# PowerConversionBoard.net
KiCad netlist of a schematic drawn in EAGLE
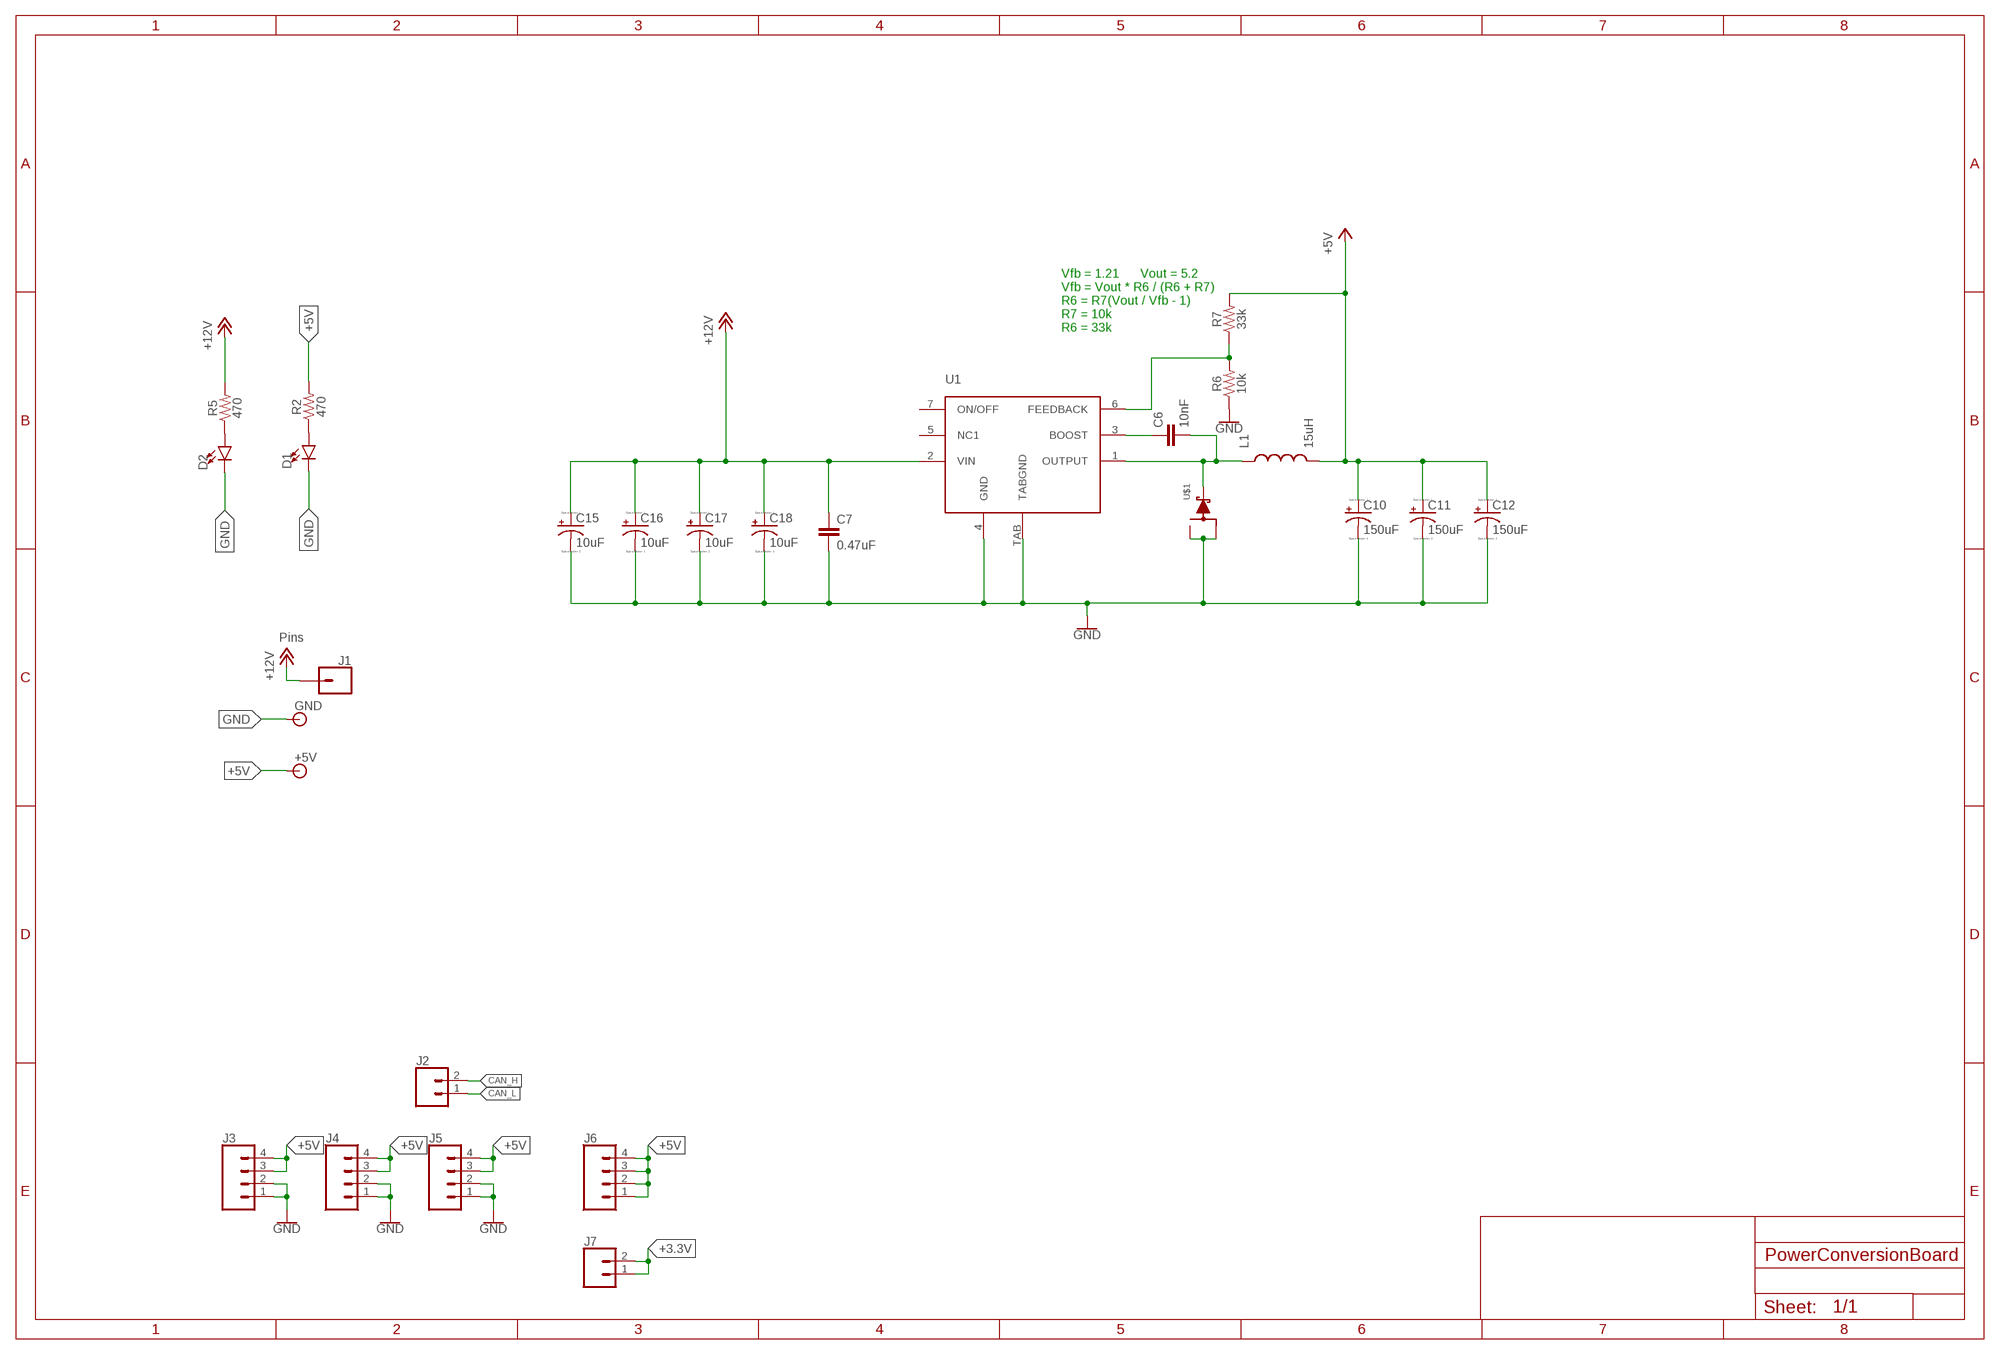
[diagram p0: schematic, sheet 1, part 1 of 3]
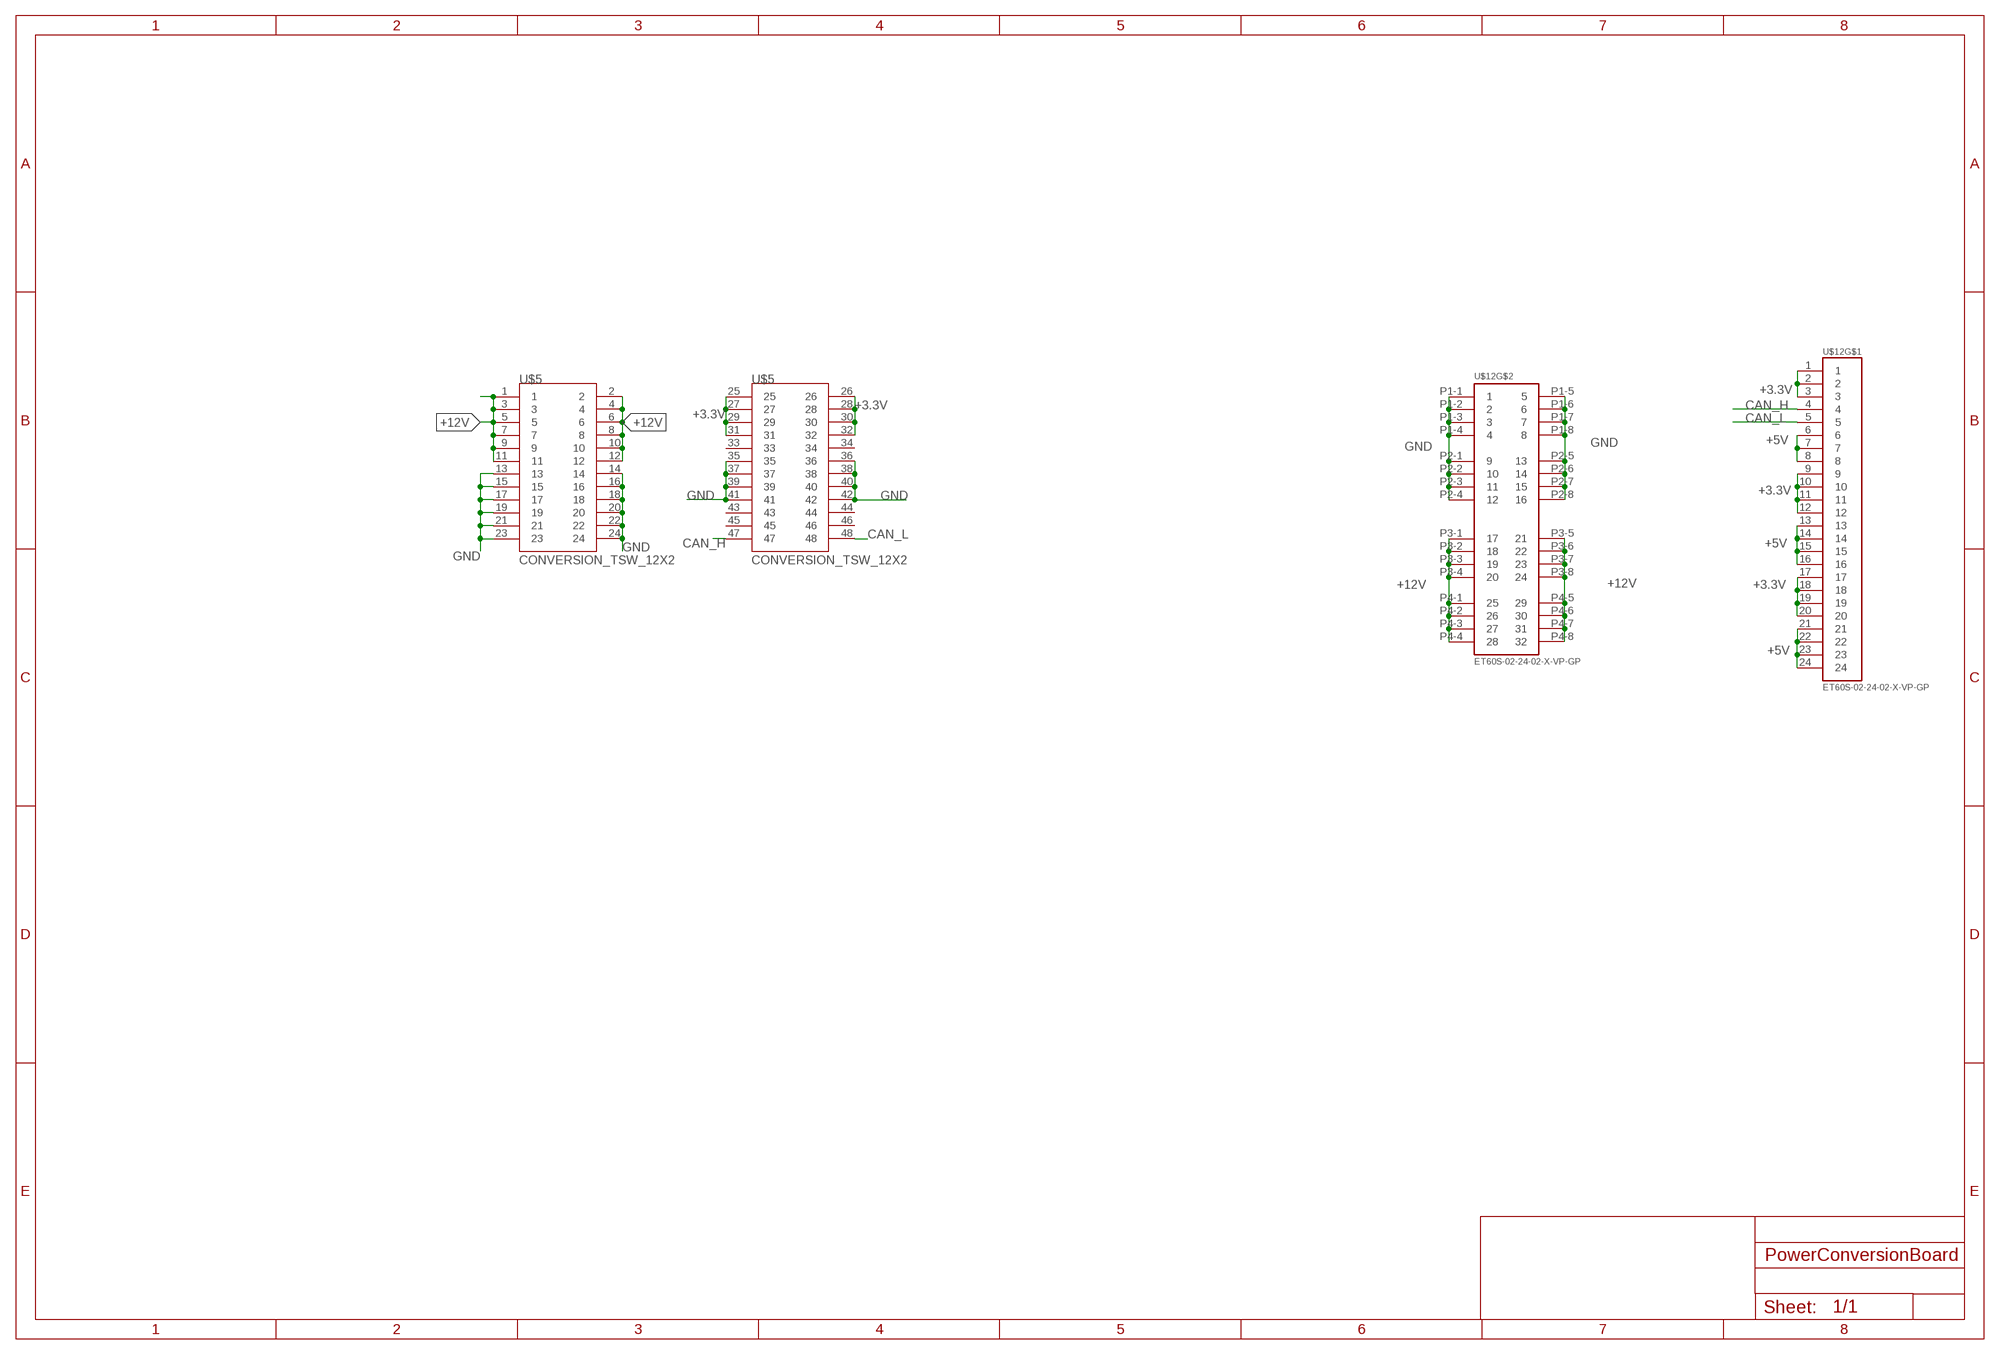
[diagram p1: schematic, sheet 1, part 2 of 3]
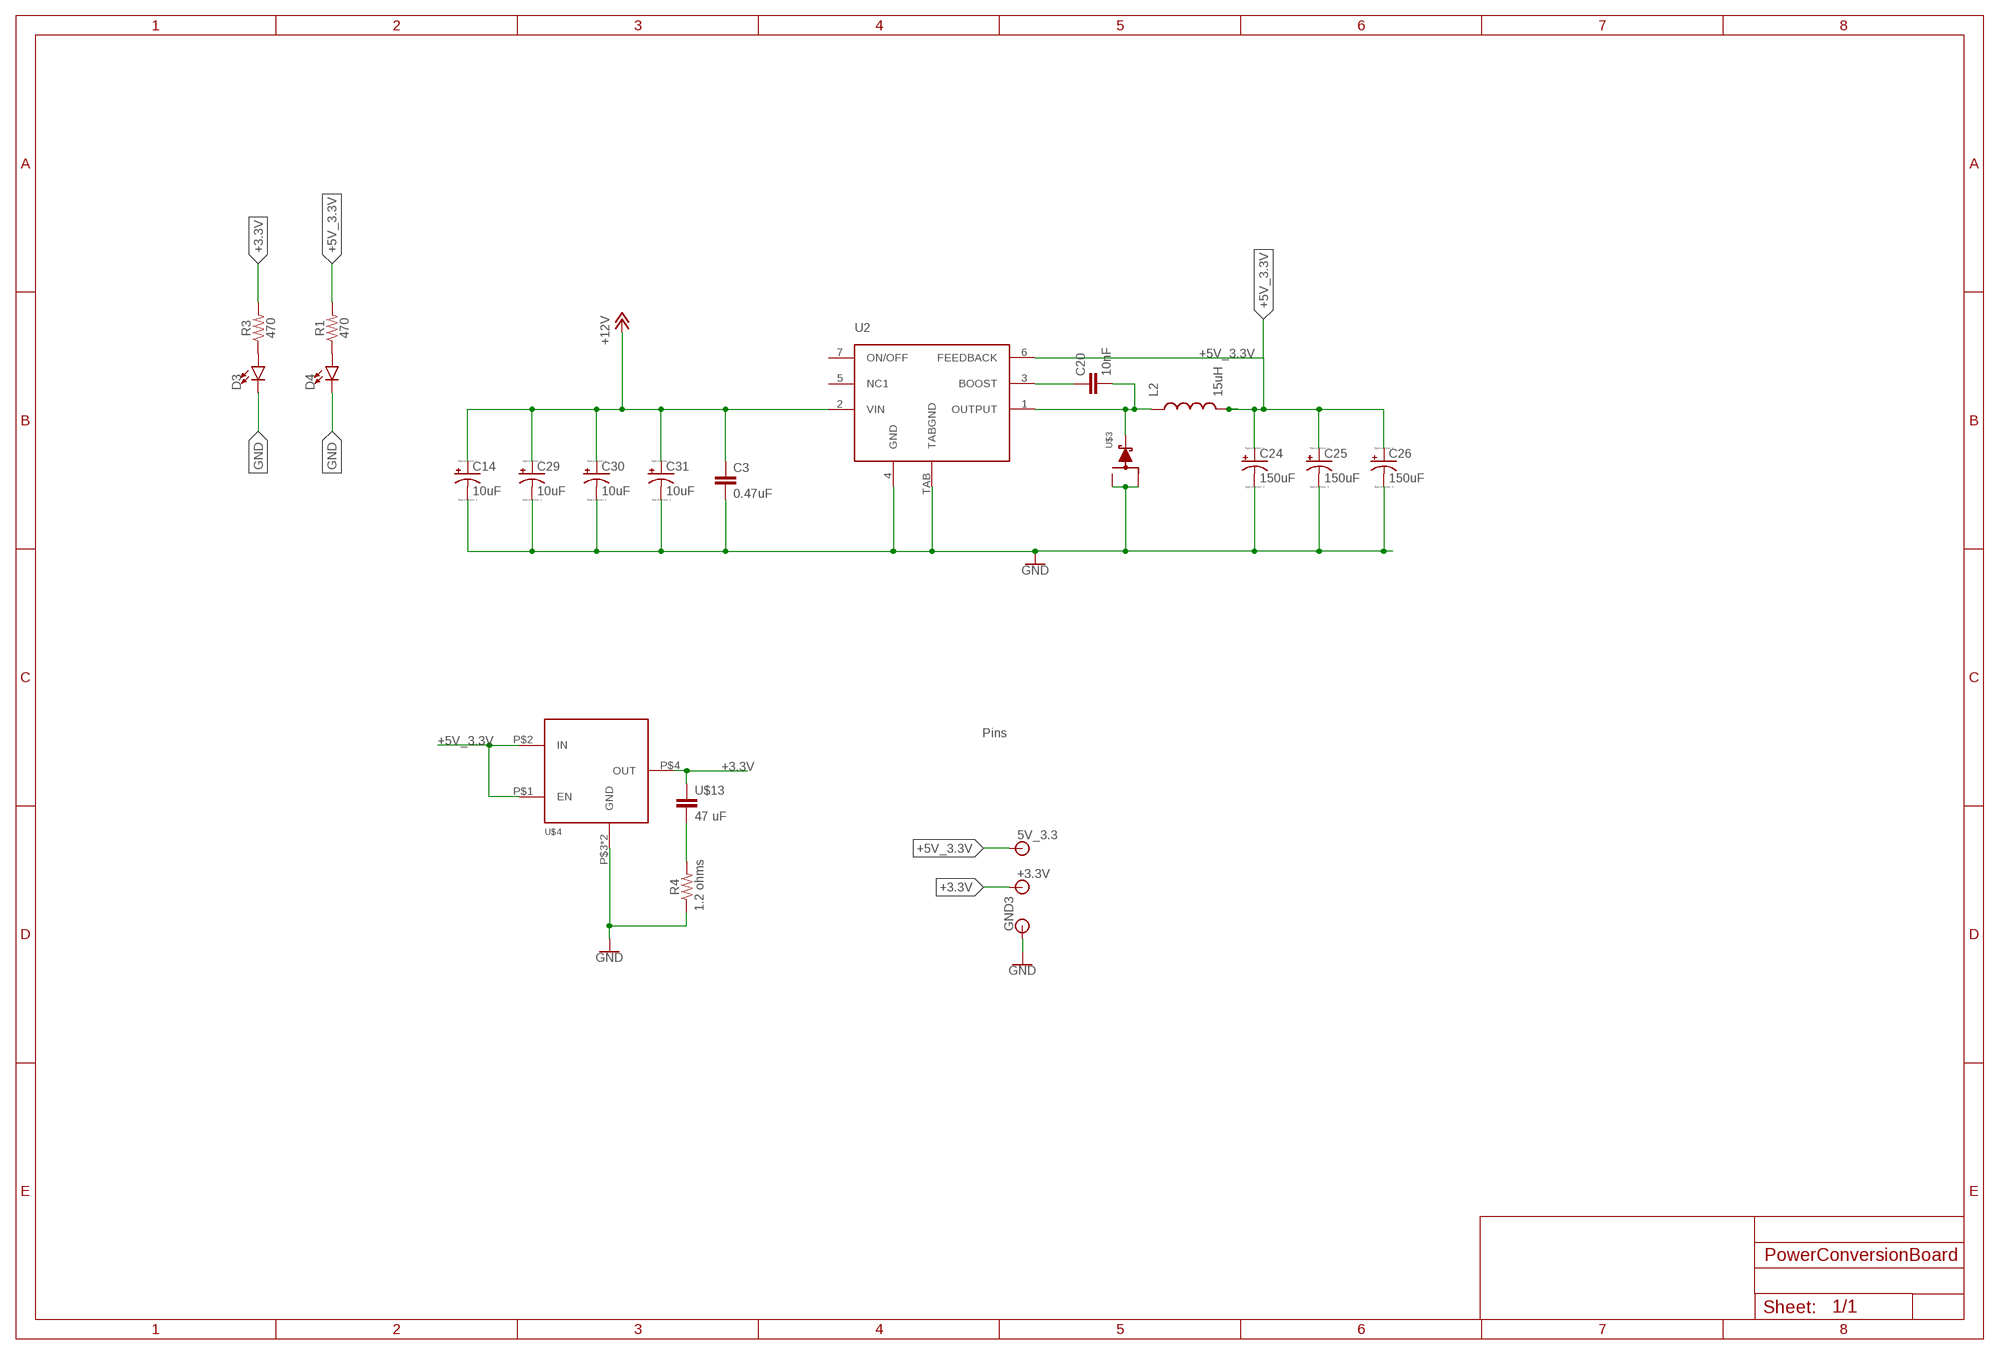
[diagram p2: schematic, sheet 1, part 3 of 3]

(export (version "E")
  (design (tool "Eeschema 10.0.6"))
  (components
    (comp (ref "+3.3V")
      (value "BANANA_CONN")
      (footprint "eagle-import:BANANA_CONN")
      (libsource (lib "eagle-import") (part "BANANA_CONN"))
    )
    (comp (ref "+5V")
      (value "BANANA_CONN")
      (footprint "eagle-import:BANANA_CONN")
      (libsource (lib "eagle-import") (part "BANANA_CONN"))
    )
    (comp (ref "5V_3.3")
      (value "BANANA_CONN")
      (footprint "eagle-import:BANANA_CONN")
      (libsource (lib "eagle-import") (part "BANANA_CONN"))
    )
    (comp (ref "C3")
      (value "0.47uF")
      (footprint "eagle-import:C0603")
      (libsource (lib "eagle-import") (part "C-EUC0603"))
    )
    (comp (ref "C6")
      (value "10nF")
      (footprint "eagle-import:0603")
      (libsource (lib "eagle-import") (part "10NF-0603-50V-10%"))
    )
    (comp (ref "C7")
      (value "0.47uF")
      (footprint "eagle-import:C0603")
      (libsource (lib "eagle-import") (part "C-EUC0603"))
    )
    (comp (ref "C10")
      (value "150uF")
      (footprint "eagle-import:CTAN(7.30_4.30MM)")
      (libsource (lib "eagle-import") (part "C-TANTALUM(10UF_150UF)"))
    )
    (comp (ref "C11")
      (value "150uF")
      (footprint "eagle-import:CTAN(7.30_4.30MM)")
      (libsource (lib "eagle-import") (part "C-TANTALUM(10UF_150UF)"))
    )
    (comp (ref "C12")
      (value "150uF")
      (footprint "eagle-import:CTAN(7.30_4.30MM)")
      (libsource (lib "eagle-import") (part "C-TANTALUM(10UF_150UF)"))
    )
    (comp (ref "C14")
      (value "10uF")
      (footprint "eagle-import:CTAN(7.30_4.30MM)")
      (libsource (lib "eagle-import") (part "C-TANTALUM(10UF_150UF)"))
    )
    (comp (ref "C15")
      (value "10uF")
      (footprint "eagle-import:CTAN(7.30_4.30MM)")
      (libsource (lib "eagle-import") (part "C-TANTALUM(10UF_150UF)"))
    )
    (comp (ref "C16")
      (value "10uF")
      (footprint "eagle-import:CTAN(7.30_4.30MM)")
      (libsource (lib "eagle-import") (part "C-TANTALUM(10UF_150UF)"))
    )
    (comp (ref "C17")
      (value "10uF")
      (footprint "eagle-import:CTAN(7.30_4.30MM)")
      (libsource (lib "eagle-import") (part "C-TANTALUM(10UF_150UF)"))
    )
    (comp (ref "C18")
      (value "10uF")
      (footprint "eagle-import:CTAN(7.30_4.30MM)")
      (libsource (lib "eagle-import") (part "C-TANTALUM(10UF_150UF)"))
    )
    (comp (ref "C20")
      (value "10nF")
      (footprint "eagle-import:0603")
      (libsource (lib "eagle-import") (part "10NF-0603-50V-10%"))
    )
    (comp (ref "C24")
      (value "150uF")
      (footprint "eagle-import:CTAN(7.30_4.30MM)")
      (libsource (lib "eagle-import") (part "C-TANTALUM(10UF_150UF)"))
    )
    (comp (ref "C25")
      (value "150uF")
      (footprint "eagle-import:CTAN(7.30_4.30MM)")
      (libsource (lib "eagle-import") (part "C-TANTALUM(10UF_150UF)"))
    )
    (comp (ref "C26")
      (value "150uF")
      (footprint "eagle-import:CTAN(7.30_4.30MM)")
      (libsource (lib "eagle-import") (part "C-TANTALUM(10UF_150UF)"))
    )
    (comp (ref "C29")
      (value "10uF")
      (footprint "eagle-import:CTAN(7.30_4.30MM)")
      (libsource (lib "eagle-import") (part "C-TANTALUM(10UF_150UF)"))
    )
    (comp (ref "C30")
      (value "10uF")
      (footprint "eagle-import:CTAN(7.30_4.30MM)")
      (libsource (lib "eagle-import") (part "C-TANTALUM(10UF_150UF)"))
    )
    (comp (ref "C31")
      (value "10uF")
      (footprint "eagle-import:CTAN(7.30_4.30MM)")
      (libsource (lib "eagle-import") (part "C-TANTALUM(10UF_150UF)"))
    )
    (comp (ref "D1")
      (value "LED0603")
      (footprint "eagle-import:LED-0603")
      (libsource (lib "eagle-import") (part "LED0603"))
    )
    (comp (ref "D2")
      (value "LED0603")
      (footprint "eagle-import:LED-0603")
      (libsource (lib "eagle-import") (part "LED0603"))
    )
    (comp (ref "D3")
      (value "LED0603")
      (footprint "eagle-import:LED-0603")
      (libsource (lib "eagle-import") (part "LED0603"))
    )
    (comp (ref "D4")
      (value "LED0603")
      (footprint "eagle-import:LED-0603")
      (libsource (lib "eagle-import") (part "LED0603"))
    )
    (comp (ref "GND")
      (value "BANANA_CONN")
      (footprint "eagle-import:BANANA_CONN")
      (libsource (lib "eagle-import") (part "BANANA_CONN"))
    )
    (comp (ref "GND3")
      (value "BANANA_CONN")
      (footprint "eagle-import:BANANA_CONN")
      (libsource (lib "eagle-import") (part "BANANA_CONN"))
    )
    (comp (ref "J1")
      (value "CONN_01")
      (footprint "eagle-import:1X01")
      (libsource (lib "eagle-import") (part "CONN_01"))
    )
    (comp (ref "J2")
      (value "CONN_02")
      (footprint "eagle-import:1X02")
      (libsource (lib "eagle-import") (part "CONN_02"))
    )
    (comp (ref "J3")
      (value "CONN_04")
      (footprint "eagle-import:1X04")
      (libsource (lib "eagle-import") (part "CONN_04"))
    )
    (comp (ref "J4")
      (value "CONN_04")
      (footprint "eagle-import:1X04")
      (libsource (lib "eagle-import") (part "CONN_04"))
    )
    (comp (ref "J5")
      (value "CONN_04")
      (footprint "eagle-import:1X04")
      (libsource (lib "eagle-import") (part "CONN_04"))
    )
    (comp (ref "J6")
      (value "CONN_04")
      (footprint "eagle-import:1X04")
      (libsource (lib "eagle-import") (part "CONN_04"))
    )
    (comp (ref "J7")
      (value "CONN_02")
      (footprint "eagle-import:1X02")
      (libsource (lib "eagle-import") (part "CONN_02"))
    )
    (comp (ref "L1")
      (value "15uH")
      (footprint "eagle-import:HCMA1305")
      (libsource (lib "eagle-import") (part "HCMA1305"))
    )
    (comp (ref "L2")
      (value "15uH")
      (footprint "eagle-import:HCMA1305")
      (libsource (lib "eagle-import") (part "HCMA1305"))
    )
    (comp (ref "R1")
      (value "470")
      (footprint "eagle-import:0603")
      (libsource (lib "eagle-import") (part "470OHM-0603-1/10W-1%"))
    )
    (comp (ref "R2")
      (value "470")
      (footprint "eagle-import:0603")
      (libsource (lib "eagle-import") (part "470OHM-0603-1/10W-1%"))
    )
    (comp (ref "R3")
      (value "470")
      (footprint "eagle-import:0603")
      (libsource (lib "eagle-import") (part "470OHM-0603-1/10W-1%"))
    )
    (comp (ref "R4")
      (value "1.2 ohms")
      (footprint "eagle-import:0603")
      (libsource (lib "eagle-import") (part "RESISTOR0603"))
    )
    (comp (ref "R5")
      (value "470")
      (footprint "eagle-import:0603")
      (libsource (lib "eagle-import") (part "470OHM-0603-1/10W-1%"))
    )
    (comp (ref "R6")
      (value "10k")
      (footprint "eagle-import:0603")
      (libsource (lib "eagle-import") (part "10KOHM-0603-1/10W-1%"))
    )
    (comp (ref "R7")
      (value "33k")
      (footprint "eagle-import:0603")
      (libsource (lib "eagle-import") (part "33KOHM-0603-1/10W-1%"))
    )
    (comp (ref "U$1")
      (value "SWITCHMODE_SCHOTTKY")
      (footprint "eagle-import:DPAK-3")
      (libsource (lib "eagle-import") (part "SWITCHMODE_SCHOTTKY"))
    )
    (comp (ref "U$3")
      (value "SWITCHMODE_SCHOTTKY")
      (footprint "eagle-import:DPAK-3")
      (libsource (lib "eagle-import") (part "SWITCHMODE_SCHOTTKY"))
    )
    (comp (ref "U$4")
      (value "TO-263")
      (footprint "eagle-import:TO-263")
      (libsource (lib "eagle-import") (part "TO-263"))
    )
    (comp (ref "U$5")
      (value "CONVERSION_TSW_12X2")
      (footprint "eagle-import:CONVERSION_TSW_12X2")
      (libsource (lib "eagle-import") (part "CONVERSION_TSW_12X2"))
    )
    (comp (ref "U$12")
      (value "ET60S-02-24-02-X-VP-GP")
      (footprint "eagle-import:ET60S-02-24-02-X-VP-GP")
      (libsource (lib "eagle-import") (part "ET60S-02-24-02-X-VP-GP"))
    )
    (comp (ref "U$13")
      (value "47 uF")
      (footprint "eagle-import:RESC0603_N")
      (libsource (lib "eagle-import") (part "CAPACITOR_0603_N"))
    )
    (comp (ref "U1")
      (value "LM2678")
      (footprint "eagle-import:LM2678")
      (libsource (lib "eagle-import") (part "LM2678"))
    )
    (comp (ref "U2")
      (value "LM2678")
      (footprint "eagle-import:LM2678")
      (libsource (lib "eagle-import") (part "LM2678"))
    )
  )
  (nets
    (net (code "1") (name "+3.3V") (class "Default")
      (node (ref "+3.3V") (pin "P$1") (pinfunction "1_P$1") (pintype "passive"))
      (node (ref "J7") (pin "1") (pinfunction "1_1") (pintype "passive"))
      (node (ref "J7") (pin "2") (pinfunction "2_2") (pintype "passive"))
      (node (ref "R3") (pin "2") (pinfunction "2_2") (pintype "passive"))
      (node (ref "U$12") (pin "1") (pinfunction "1_1") (pintype "bidirectional"))
      (node (ref "U$12") (pin "10") (pinfunction "10_10") (pintype "bidirectional"))
      (node (ref "U$12") (pin "11") (pinfunction "11_11") (pintype "bidirectional"))
      (node (ref "U$12") (pin "12") (pinfunction "12_12") (pintype "bidirectional"))
      (node (ref "U$12") (pin "17") (pinfunction "17_17") (pintype "bidirectional"))
      (node (ref "U$12") (pin "18") (pinfunction "18_18") (pintype "bidirectional"))
      (node (ref "U$12") (pin "19") (pinfunction "19_19") (pintype "bidirectional"))
      (node (ref "U$12") (pin "2") (pinfunction "2_2") (pintype "bidirectional"))
      (node (ref "U$12") (pin "20") (pinfunction "20_20") (pintype "bidirectional"))
      (node (ref "U$12") (pin "3") (pinfunction "3_3") (pintype "bidirectional"))
      (node (ref "U$12") (pin "9") (pinfunction "9_9") (pintype "bidirectional"))
      (node (ref "U$13") (pin "1") (pinfunction "1_1") (pintype "passive"))
      (node (ref "U$4") (pin "P$4") (pinfunction "OUT_P$4") (pintype "bidirectional"))
      (node (ref "U$5") (pin "25") (pinfunction "25_25") (pintype "bidirectional"))
      (node (ref "U$5") (pin "26") (pinfunction "26_26") (pintype "bidirectional"))
      (node (ref "U$5") (pin "27") (pinfunction "27_27") (pintype "bidirectional"))
      (node (ref "U$5") (pin "28") (pinfunction "28_28") (pintype "bidirectional"))
      (node (ref "U$5") (pin "29") (pinfunction "29_29") (pintype "bidirectional"))
      (node (ref "U$5") (pin "30") (pinfunction "30_30") (pintype "bidirectional"))
      (node (ref "U$5") (pin "31") (pinfunction "31_31") (pintype "bidirectional"))
      (node (ref "U$5") (pin "32") (pinfunction "32_32") (pintype "bidirectional"))
    )
    (net (code "2") (name "+5V") (class "Default")
      (node (ref "+5V") (pin "P$1") (pinfunction "1_P$1") (pintype "passive"))
      (node (ref "C10") (pin "+") (pinfunction "+_+") (pintype "passive"))
      (node (ref "C11") (pin "+") (pinfunction "+_+") (pintype "passive"))
      (node (ref "C12") (pin "+") (pinfunction "+_+") (pintype "passive"))
      (node (ref "J3") (pin "3") (pinfunction "3_3") (pintype "passive"))
      (node (ref "J3") (pin "4") (pinfunction "4_4") (pintype "passive"))
      (node (ref "J4") (pin "3") (pinfunction "3_3") (pintype "passive"))
      (node (ref "J4") (pin "4") (pinfunction "4_4") (pintype "passive"))
      (node (ref "J5") (pin "3") (pinfunction "3_3") (pintype "passive"))
      (node (ref "J5") (pin "4") (pinfunction "4_4") (pintype "passive"))
      (node (ref "J6") (pin "1") (pinfunction "1_1") (pintype "passive"))
      (node (ref "J6") (pin "2") (pinfunction "2_2") (pintype "passive"))
      (node (ref "J6") (pin "3") (pinfunction "3_3") (pintype "passive"))
      (node (ref "J6") (pin "4") (pinfunction "4_4") (pintype "passive"))
      (node (ref "L1") (pin "2") (pinfunction "2_2") (pintype "passive"))
      (node (ref "R2") (pin "2") (pinfunction "2_2") (pintype "passive"))
      (node (ref "R7") (pin "2") (pinfunction "2_2") (pintype "passive"))
      (node (ref "U$12") (pin "13") (pinfunction "13_13") (pintype "bidirectional"))
      (node (ref "U$12") (pin "14") (pinfunction "14_14") (pintype "bidirectional"))
      (node (ref "U$12") (pin "15") (pinfunction "15_15") (pintype "bidirectional"))
      (node (ref "U$12") (pin "16") (pinfunction "16_16") (pintype "bidirectional"))
      (node (ref "U$12") (pin "21") (pinfunction "21_21") (pintype "bidirectional"))
      (node (ref "U$12") (pin "22") (pinfunction "22_22") (pintype "bidirectional"))
      (node (ref "U$12") (pin "23") (pinfunction "23_23") (pintype "bidirectional"))
      (node (ref "U$12") (pin "24") (pinfunction "24_24") (pintype "bidirectional"))
      (node (ref "U$12") (pin "6") (pinfunction "6_6") (pintype "bidirectional"))
      (node (ref "U$12") (pin "7") (pinfunction "7_7") (pintype "bidirectional"))
      (node (ref "U$12") (pin "8") (pinfunction "8_8") (pintype "bidirectional"))
    )
    (net (code "3") (name "+5V_3.3V") (class "Default")
      (node (ref "5V_3.3") (pin "P$1") (pinfunction "1_P$1") (pintype "passive"))
      (node (ref "C24") (pin "+") (pinfunction "+_+") (pintype "passive"))
      (node (ref "C25") (pin "+") (pinfunction "+_+") (pintype "passive"))
      (node (ref "C26") (pin "+") (pinfunction "+_+") (pintype "passive"))
      (node (ref "L2") (pin "2") (pinfunction "2_2") (pintype "passive"))
      (node (ref "R1") (pin "2") (pinfunction "2_2") (pintype "passive"))
      (node (ref "U$4") (pin "P$1") (pinfunction "EN_P$1") (pintype "bidirectional"))
      (node (ref "U$4") (pin "P$2") (pinfunction "IN_P$2") (pintype "bidirectional"))
      (node (ref "U2") (pin "6") (pinfunction "FEEDBACK_6") (pintype "bidirectional"))
    )
    (net (code "4") (name "+12V") (class "Default")
      (node (ref "C14") (pin "+") (pinfunction "+_+") (pintype "passive"))
      (node (ref "C15") (pin "+") (pinfunction "+_+") (pintype "passive"))
      (node (ref "C16") (pin "+") (pinfunction "+_+") (pintype "passive"))
      (node (ref "C17") (pin "+") (pinfunction "+_+") (pintype "passive"))
      (node (ref "C18") (pin "+") (pinfunction "+_+") (pintype "passive"))
      (node (ref "C29") (pin "+") (pinfunction "+_+") (pintype "passive"))
      (node (ref "C3") (pin "1") (pinfunction "1_1") (pintype "passive"))
      (node (ref "C30") (pin "+") (pinfunction "+_+") (pintype "passive"))
      (node (ref "C31") (pin "+") (pinfunction "+_+") (pintype "passive"))
      (node (ref "C7") (pin "1") (pinfunction "1_1") (pintype "passive"))
      (node (ref "J1") (pin "1") (pinfunction "1_1") (pintype "passive"))
      (node (ref "R5") (pin "2") (pinfunction "2_2") (pintype "passive"))
      (node (ref "U$12") (pin "P3-1") (pinfunction "17_P3-1") (pintype "bidirectional"))
      (node (ref "U$12") (pin "P3-2") (pinfunction "18_P3-2") (pintype "bidirectional"))
      (node (ref "U$12") (pin "P3-3") (pinfunction "19_P3-3") (pintype "bidirectional"))
      (node (ref "U$12") (pin "P3-4") (pinfunction "20_P3-4") (pintype "bidirectional"))
      (node (ref "U$12") (pin "P3-5") (pinfunction "21_P3-5") (pintype "bidirectional"))
      (node (ref "U$12") (pin "P3-6") (pinfunction "22_P3-6") (pintype "bidirectional"))
      (node (ref "U$12") (pin "P3-7") (pinfunction "23_P3-7") (pintype "bidirectional"))
      (node (ref "U$12") (pin "P3-8") (pinfunction "24_P3-8") (pintype "bidirectional"))
      (node (ref "U$12") (pin "P4-1") (pinfunction "25_P4-1") (pintype "bidirectional"))
      (node (ref "U$12") (pin "P4-2") (pinfunction "26_P4-2") (pintype "bidirectional"))
      (node (ref "U$12") (pin "P4-3") (pinfunction "27_P4-3") (pintype "bidirectional"))
      (node (ref "U$12") (pin "P4-4") (pinfunction "28_P4-4") (pintype "bidirectional"))
      (node (ref "U$12") (pin "P4-5") (pinfunction "29_P4-5") (pintype "bidirectional"))
      (node (ref "U$12") (pin "P4-6") (pinfunction "30_P4-6") (pintype "bidirectional"))
      (node (ref "U$12") (pin "P4-7") (pinfunction "31_P4-7") (pintype "bidirectional"))
      (node (ref "U$12") (pin "P4-8") (pinfunction "32_P4-8") (pintype "bidirectional"))
      (node (ref "U$5") (pin "1") (pinfunction "1_1") (pintype "bidirectional"))
      (node (ref "U$5") (pin "10") (pinfunction "10_10") (pintype "bidirectional"))
      (node (ref "U$5") (pin "11") (pinfunction "11_11") (pintype "bidirectional"))
      (node (ref "U$5") (pin "12") (pinfunction "12_12") (pintype "bidirectional"))
      (node (ref "U$5") (pin "2") (pinfunction "2_2") (pintype "bidirectional"))
      (node (ref "U$5") (pin "3") (pinfunction "3_3") (pintype "bidirectional"))
      (node (ref "U$5") (pin "4") (pinfunction "4_4") (pintype "bidirectional"))
      (node (ref "U$5") (pin "5") (pinfunction "5_5") (pintype "bidirectional"))
      (node (ref "U$5") (pin "6") (pinfunction "6_6") (pintype "bidirectional"))
      (node (ref "U$5") (pin "7") (pinfunction "7_7") (pintype "bidirectional"))
      (node (ref "U$5") (pin "8") (pinfunction "8_8") (pintype "bidirectional"))
      (node (ref "U$5") (pin "9") (pinfunction "9_9") (pintype "bidirectional"))
      (node (ref "U1") (pin "2") (pinfunction "VIN_2") (pintype "bidirectional"))
      (node (ref "U2") (pin "2") (pinfunction "VIN_2") (pintype "bidirectional"))
    )
    (net (code "5") (name "CAN_H") (class "Default")
      (node (ref "J2") (pin "2") (pinfunction "2_2") (pintype "passive"))
      (node (ref "U$12") (pin "4") (pinfunction "4_4") (pintype "bidirectional"))
      (node (ref "U$5") (pin "47") (pinfunction "47_47") (pintype "bidirectional"))
    )
    (net (code "6") (name "CAN_L") (class "Default")
      (node (ref "J2") (pin "1") (pinfunction "1_1") (pintype "passive"))
      (node (ref "U$12") (pin "5") (pinfunction "5_5") (pintype "bidirectional"))
      (node (ref "U$5") (pin "48") (pinfunction "48_48") (pintype "bidirectional"))
    )
    (net (code "7") (name "GND") (class "Default")
      (node (ref "C10") (pin "-") (pinfunction "-_-") (pintype "passive"))
      (node (ref "C11") (pin "-") (pinfunction "-_-") (pintype "passive"))
      (node (ref "C12") (pin "-") (pinfunction "-_-") (pintype "passive"))
      (node (ref "C14") (pin "-") (pinfunction "-_-") (pintype "passive"))
      (node (ref "C15") (pin "-") (pinfunction "-_-") (pintype "passive"))
      (node (ref "C16") (pin "-") (pinfunction "-_-") (pintype "passive"))
      (node (ref "C17") (pin "-") (pinfunction "-_-") (pintype "passive"))
      (node (ref "C18") (pin "-") (pinfunction "-_-") (pintype "passive"))
      (node (ref "C24") (pin "-") (pinfunction "-_-") (pintype "passive"))
      (node (ref "C25") (pin "-") (pinfunction "-_-") (pintype "passive"))
      (node (ref "C26") (pin "-") (pinfunction "-_-") (pintype "passive"))
      (node (ref "C29") (pin "-") (pinfunction "-_-") (pintype "passive"))
      (node (ref "C3") (pin "2") (pinfunction "2_2") (pintype "passive"))
      (node (ref "C30") (pin "-") (pinfunction "-_-") (pintype "passive"))
      (node (ref "C31") (pin "-") (pinfunction "-_-") (pintype "passive"))
      (node (ref "C7") (pin "2") (pinfunction "2_2") (pintype "passive"))
      (node (ref "D1") (pin "C") (pinfunction "C_C") (pintype "passive"))
      (node (ref "D2") (pin "C") (pinfunction "C_C") (pintype "passive"))
      (node (ref "D3") (pin "C") (pinfunction "C_C") (pintype "passive"))
      (node (ref "D4") (pin "C") (pinfunction "C_C") (pintype "passive"))
      (node (ref "GND") (pin "P$1") (pinfunction "1_P$1") (pintype "passive"))
      (node (ref "GND3") (pin "P$1") (pinfunction "1_P$1") (pintype "passive"))
      (node (ref "J3") (pin "1") (pinfunction "1_1") (pintype "passive"))
      (node (ref "J3") (pin "2") (pinfunction "2_2") (pintype "passive"))
      (node (ref "J4") (pin "1") (pinfunction "1_1") (pintype "passive"))
      (node (ref "J4") (pin "2") (pinfunction "2_2") (pintype "passive"))
      (node (ref "J5") (pin "1") (pinfunction "1_1") (pintype "passive"))
      (node (ref "J5") (pin "2") (pinfunction "2_2") (pintype "passive"))
      (node (ref "R4") (pin "1") (pinfunction "1_1") (pintype "passive"))
      (node (ref "R6") (pin "1") (pinfunction "1_1") (pintype "passive"))
      (node (ref "U$1") (pin "P$1") (pinfunction "P$1_P$1") (pintype "bidirectional"))
      (node (ref "U$1") (pin "P$3") (pinfunction "P$3_P$3") (pintype "bidirectional"))
      (node (ref "U$12") (pin "P1-1") (pinfunction "1_P1-1") (pintype "bidirectional"))
      (node (ref "U$12") (pin "P1-2") (pinfunction "2_P1-2") (pintype "bidirectional"))
      (node (ref "U$12") (pin "P1-3") (pinfunction "3_P1-3") (pintype "bidirectional"))
      (node (ref "U$12") (pin "P1-4") (pinfunction "4_P1-4") (pintype "bidirectional"))
      (node (ref "U$12") (pin "P1-5") (pinfunction "5_P1-5") (pintype "bidirectional"))
      (node (ref "U$12") (pin "P1-6") (pinfunction "6_P1-6") (pintype "bidirectional"))
      (node (ref "U$12") (pin "P1-7") (pinfunction "7_P1-7") (pintype "bidirectional"))
      (node (ref "U$12") (pin "P1-8") (pinfunction "8_P1-8") (pintype "bidirectional"))
      (node (ref "U$12") (pin "P2-1") (pinfunction "9_P2-1") (pintype "bidirectional"))
      (node (ref "U$12") (pin "P2-2") (pinfunction "10_P2-2") (pintype "bidirectional"))
      (node (ref "U$12") (pin "P2-3") (pinfunction "11_P2-3") (pintype "bidirectional"))
      (node (ref "U$12") (pin "P2-4") (pinfunction "12_P2-4") (pintype "bidirectional"))
      (node (ref "U$12") (pin "P2-5") (pinfunction "13_P2-5") (pintype "bidirectional"))
      (node (ref "U$12") (pin "P2-6") (pinfunction "14_P2-6") (pintype "bidirectional"))
      (node (ref "U$12") (pin "P2-7") (pinfunction "15_P2-7") (pintype "bidirectional"))
      (node (ref "U$12") (pin "P2-8") (pinfunction "16_P2-8") (pintype "bidirectional"))
      (node (ref "U$3") (pin "P$1") (pinfunction "P$1_P$1") (pintype "bidirectional"))
      (node (ref "U$3") (pin "P$3") (pinfunction "P$3_P$3") (pintype "bidirectional"))
      (node (ref "U$4") (pin "P$3") (pinfunction "GND_P$3") (pintype "bidirectional"))
      (node (ref "U$4") (pin "P$6") (pinfunction "GND_P$6") (pintype "bidirectional"))
      (node (ref "U$5") (pin "13") (pinfunction "13_13") (pintype "bidirectional"))
      (node (ref "U$5") (pin "14") (pinfunction "14_14") (pintype "bidirectional"))
      (node (ref "U$5") (pin "15") (pinfunction "15_15") (pintype "bidirectional"))
      (node (ref "U$5") (pin "16") (pinfunction "16_16") (pintype "bidirectional"))
      (node (ref "U$5") (pin "17") (pinfunction "17_17") (pintype "bidirectional"))
      (node (ref "U$5") (pin "18") (pinfunction "18_18") (pintype "bidirectional"))
      (node (ref "U$5") (pin "19") (pinfunction "19_19") (pintype "bidirectional"))
      (node (ref "U$5") (pin "20") (pinfunction "20_20") (pintype "bidirectional"))
      (node (ref "U$5") (pin "21") (pinfunction "21_21") (pintype "bidirectional"))
      (node (ref "U$5") (pin "22") (pinfunction "22_22") (pintype "bidirectional"))
      (node (ref "U$5") (pin "23") (pinfunction "23_23") (pintype "bidirectional"))
      (node (ref "U$5") (pin "24") (pinfunction "24_24") (pintype "bidirectional"))
      (node (ref "U$5") (pin "35") (pinfunction "35_35") (pintype "bidirectional"))
      (node (ref "U$5") (pin "36") (pinfunction "36_36") (pintype "bidirectional"))
      (node (ref "U$5") (pin "37") (pinfunction "37_37") (pintype "bidirectional"))
      (node (ref "U$5") (pin "38") (pinfunction "38_38") (pintype "bidirectional"))
      (node (ref "U$5") (pin "39") (pinfunction "39_39") (pintype "bidirectional"))
      (node (ref "U$5") (pin "40") (pinfunction "40_40") (pintype "bidirectional"))
      (node (ref "U$5") (pin "41") (pinfunction "41_41") (pintype "bidirectional"))
      (node (ref "U$5") (pin "42") (pinfunction "42_42") (pintype "bidirectional"))
      (node (ref "U1") (pin "4") (pinfunction "GND_4") (pintype "bidirectional"))
      (node (ref "U1") (pin "TAB") (pinfunction "TABGND_TAB") (pintype "bidirectional"))
      (node (ref "U2") (pin "4") (pinfunction "GND_4") (pintype "bidirectional"))
      (node (ref "U2") (pin "TAB") (pinfunction "TABGND_TAB") (pintype "bidirectional"))
    )
    (net (code "8") (name "Net-(D1-PadA)") (class "Default")
      (node (ref "D1") (pin "A") (pinfunction "A_A") (pintype "passive"))
      (node (ref "R2") (pin "1") (pinfunction "1_1") (pintype "passive"))
    )
    (net (code "9") (name "Net-(D2-PadA)") (class "Default")
      (node (ref "D2") (pin "A") (pinfunction "A_A") (pintype "passive"))
      (node (ref "R5") (pin "1") (pinfunction "1_1") (pintype "passive"))
    )
    (net (code "10") (name "Net-(D3-PadA)") (class "Default")
      (node (ref "D3") (pin "A") (pinfunction "A_A") (pintype "passive"))
      (node (ref "R3") (pin "1") (pinfunction "1_1") (pintype "passive"))
    )
    (net (code "11") (name "Net-(D4-PadA)") (class "Default")
      (node (ref "D4") (pin "A") (pinfunction "A_A") (pintype "passive"))
      (node (ref "R1") (pin "1") (pinfunction "1_1") (pintype "passive"))
    )
    (net (code "12") (name "Net-(R4-Pad2)") (class "Default")
      (node (ref "R4") (pin "2") (pinfunction "2_2") (pintype "passive"))
      (node (ref "U$13") (pin "2") (pinfunction "2_2") (pintype "passive"))
    )
    (net (code "13") (name "Net-(U1-BOOST)") (class "Default")
      (node (ref "C6") (pin "1") (pinfunction "1_1") (pintype "passive"))
      (node (ref "U1") (pin "3") (pinfunction "BOOST_3") (pintype "bidirectional"))
    )
    (net (code "14") (name "Net-(U1-FEEDBACK)") (class "Default")
      (node (ref "R6") (pin "2") (pinfunction "2_2") (pintype "passive"))
      (node (ref "R7") (pin "1") (pinfunction "1_1") (pintype "passive"))
      (node (ref "U1") (pin "6") (pinfunction "FEEDBACK_6") (pintype "bidirectional"))
    )
    (net (code "15") (name "Net-(U1-OUTPUT)") (class "Default")
      (node (ref "C6") (pin "2") (pinfunction "2_2") (pintype "passive"))
      (node (ref "L1") (pin "1") (pinfunction "1_1") (pintype "passive"))
      (node (ref "U$1") (pin "P$4") (pinfunction "P$4_P$4") (pintype "bidirectional"))
      (node (ref "U1") (pin "1") (pinfunction "OUTPUT_1") (pintype "bidirectional"))
    )
    (net (code "16") (name "Net-(U2-BOOST)") (class "Default")
      (node (ref "C20") (pin "1") (pinfunction "1_1") (pintype "passive"))
      (node (ref "U2") (pin "3") (pinfunction "BOOST_3") (pintype "bidirectional"))
    )
    (net (code "17") (name "Net-(U2-OUTPUT)") (class "Default")
      (node (ref "C20") (pin "2") (pinfunction "2_2") (pintype "passive"))
      (node (ref "L2") (pin "1") (pinfunction "1_1") (pintype "passive"))
      (node (ref "U$3") (pin "P$4") (pinfunction "P$4_P$4") (pintype "bidirectional"))
      (node (ref "U2") (pin "1") (pinfunction "OUTPUT_1") (pintype "bidirectional"))
    )
    (net (code "18") (name "unconnected-(U$5-Pad33)") (class "Default")
      (node (ref "U$5") (pin "33") (pinfunction "33_33") (pintype "bidirectional"))
    )
    (net (code "19") (name "unconnected-(U$5-Pad34)") (class "Default")
      (node (ref "U$5") (pin "34") (pinfunction "34_34") (pintype "bidirectional"))
    )
    (net (code "20") (name "unconnected-(U$5-Pad43)") (class "Default")
      (node (ref "U$5") (pin "43") (pinfunction "43_43") (pintype "bidirectional"))
    )
    (net (code "21") (name "unconnected-(U$5-Pad44)") (class "Default")
      (node (ref "U$5") (pin "44") (pinfunction "44_44") (pintype "bidirectional"))
    )
    (net (code "22") (name "unconnected-(U$5-Pad45)") (class "Default")
      (node (ref "U$5") (pin "45") (pinfunction "45_45") (pintype "bidirectional"))
    )
    (net (code "23") (name "unconnected-(U$5-Pad46)") (class "Default")
      (node (ref "U$5") (pin "46") (pinfunction "46_46") (pintype "bidirectional"))
    )
    (net (code "24") (name "unconnected-(U1-NC1-Pad5)") (class "Default")
      (node (ref "U1") (pin "5") (pinfunction "NC1_5") (pintype "no_connect"))
    )
    (net (code "25") (name "unconnected-(U1-ON{slash}OFF-Pad7)") (class "Default")
      (node (ref "U1") (pin "7") (pinfunction "ON/OFF_7") (pintype "bidirectional"))
    )
    (net (code "26") (name "unconnected-(U2-NC1-Pad5)") (class "Default")
      (node (ref "U2") (pin "5") (pinfunction "NC1_5") (pintype "no_connect"))
    )
    (net (code "27") (name "unconnected-(U2-ON{slash}OFF-Pad7)") (class "Default")
      (node (ref "U2") (pin "7") (pinfunction "ON/OFF_7") (pintype "bidirectional"))
    )
  )
)
